# MCU.net
KiCad netlist of a schematic drawn in Altium Designer
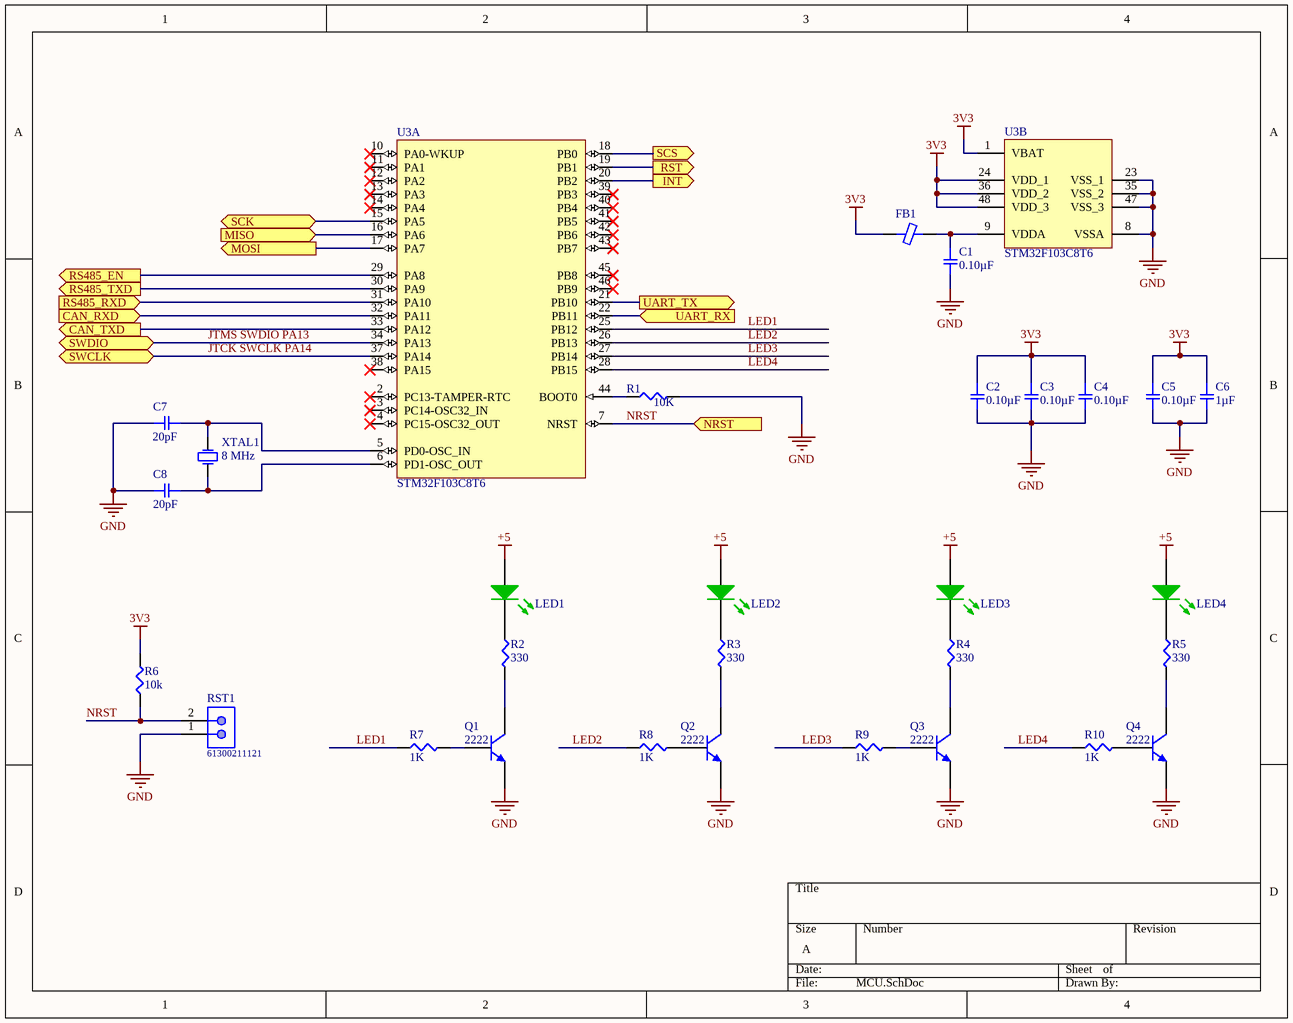
[diagram p0: MCU.SchDoc]

(export (version "E")
  (design (tool "Eeschema 10.0.6"))
  (components
    (comp (ref "C1")
      (value "0.10µF")
      (footprint "0805")
      (description "CAP CER 0.1UF 25V X7R 0805")
      (fields
        (field (name "DIGI-KEY PART NUMBER") "490-12754-1-ND")
        (field (name "PART NUMBER") "GRM219R71E104KA01D")
      )
      (libsource (lib "Cap_805") (part "GRM219R71E104KA01D"))
    )
    (comp (ref "C2")
      (value "0.10µF")
      (footprint "0805")
      (description "CAP CER 0.1UF 25V X7R 0805")
      (fields
        (field (name "DIGI-KEY PART NUMBER") "490-12754-1-ND")
        (field (name "PART NUMBER") "GRM219R71E104KA01D")
      )
      (libsource (lib "Cap_805") (part "GRM219R71E104KA01D"))
    )
    (comp (ref "C3")
      (value "0.10µF")
      (footprint "0805")
      (description "CAP CER 0.1UF 25V X7R 0805")
      (fields
        (field (name "DIGI-KEY PART NUMBER") "490-12754-1-ND")
        (field (name "PART NUMBER") "GRM219R71E104KA01D")
      )
      (libsource (lib "Cap_805") (part "GRM219R71E104KA01D"))
    )
    (comp (ref "C4")
      (value "0.10µF")
      (footprint "0805")
      (description "CAP CER 0.1UF 25V X7R 0805")
      (fields
        (field (name "DIGI-KEY PART NUMBER") "490-12754-1-ND")
        (field (name "PART NUMBER") "GRM219R71E104KA01D")
      )
      (libsource (lib "Cap_805") (part "GRM219R71E104KA01D"))
    )
    (comp (ref "C5")
      (value "0.10µF")
      (footprint "0805")
      (description "CAP CER 0.1UF 25V X7R 0805")
      (fields
        (field (name "DIGI-KEY PART NUMBER") "490-12754-1-ND")
        (field (name "PART NUMBER") "GRM219R71E104KA01D")
      )
      (libsource (lib "Cap_805") (part "GRM219R71E104KA01D"))
    )
    (comp (ref "C6")
      (value "1µF")
      (footprint "0805")
      (description "CAP CER 1.0UF 16V X7R 0805")
      (fields
        (field (name "DIGI-KEY PART NUMBER") "490-12590-1-ND")
        (field (name "PART NUMBER") "GCM219R71C105KA37J")
      )
      (libsource (lib "Cap_805") (part "GCM219R71C105KA37J"))
    )
    (comp (ref "C7")
      (value "20pF")
      (footprint "0805")
      (description "CAP CER 20PF 50V NP0 0805")
      (fields
        (field (name "DIGI-KEY PART NUMBER") "490-3607-1-ND")
        (field (name "PART NUMBER") "GQM2195C1H200JB01D")
      )
      (libsource (lib "Cap_805") (part "GQM2195C1H200JB01D"))
    )
    (comp (ref "C8")
      (value "20pF")
      (footprint "0805")
      (description "CAP CER 20PF 50V NP0 0805")
      (fields
        (field (name "DIGI-KEY PART NUMBER") "490-3607-1-ND")
        (field (name "PART NUMBER") "GQM2195C1H200JB01D")
      )
      (libsource (lib "Cap_805") (part "GQM2195C1H200JB01D"))
    )
    (comp (ref "FB1")
      (value "~")
      (footprint "0805")
      (description "FERRITE BEAD 0805 1LN")
      (fields
        (field (name "PART NUMBER") "2508053007Y3")
        (field (name "MANUFACTURER") "Fair-Rite Products Corp.")
      )
      (libsource (lib "Celestial Altium Library - altium_library") (part "Ferrite Chip"))
    )
    (comp (ref "LED1")
      (value "LED-GREEN")
      (footprint "DIOSMD1206")
      (description "General Propuse Ga/As LED")
      (libsource (lib "GeneralLibrary") (part "LED-GREEN"))
    )
    (comp (ref "LED2")
      (value "LED-GREEN")
      (footprint "DIOSMD1206")
      (description "General Propuse Ga/As LED")
      (libsource (lib "GeneralLibrary") (part "LED-GREEN"))
    )
    (comp (ref "LED3")
      (value "LED-GREEN")
      (footprint "DIOSMD1206")
      (description "General Propuse Ga/As LED")
      (libsource (lib "GeneralLibrary") (part "LED-GREEN"))
    )
    (comp (ref "LED4")
      (value "LED-GREEN")
      (footprint "DIOSMD1206")
      (description "General Propuse Ga/As LED")
      (libsource (lib "GeneralLibrary") (part "LED-GREEN"))
    )
    (comp (ref "Q1")
      (value "2222")
      (footprint "SOT23-3")
      (description "NPN General Purpose Amplifier")
      (fields (field (name "PUBLISHER") "Altium Limited"))
      (libsource (lib "GeneralLibrary") (part "BC817-25"))
    )
    (comp (ref "Q2")
      (value "2222")
      (footprint "SOT23-3")
      (description "NPN General Purpose Amplifier")
      (fields (field (name "PUBLISHER") "Altium Limited"))
      (libsource (lib "GeneralLibrary") (part "BC817-25"))
    )
    (comp (ref "Q3")
      (value "2222")
      (footprint "SOT23-3")
      (description "NPN General Purpose Amplifier")
      (fields (field (name "PUBLISHER") "Altium Limited"))
      (libsource (lib "GeneralLibrary") (part "BC817-25"))
    )
    (comp (ref "Q4")
      (value "2222")
      (footprint "SOT23-3")
      (description "NPN General Purpose Amplifier")
      (fields (field (name "PUBLISHER") "Altium Limited"))
      (libsource (lib "GeneralLibrary") (part "BC817-25"))
    )
    (comp (ref "R1")
      (value "10K")
      (footprint "0805")
      (description "RES SMD 10K OHM 5% 1/8W 0805")
      (fields (field (name "PART NUMBER") "ERJ-6GEYJ103V") (field (name "DIGI-KEY PART NUMBER") "P10KACT-ND"))
      (libsource (lib "Res_805") (part "ERJ-6GEYJ103V"))
    )
    (comp (ref "R2")
      (value "330")
      (footprint "0805")
      (description "RES SMD 330 OHM 5% 1/8W 0805")
      (fields (field (name "PART NUMBER") "ERJ-6GEYJ331V") (field (name "DIGI-KEY PART NUMBER") "P330ACT-ND"))
      (libsource (lib "Res_805") (part "ERJ-6GEYJ331V"))
    )
    (comp (ref "R3")
      (value "330")
      (footprint "0805")
      (description "RES SMD 330 OHM 5% 1/8W 0805")
      (fields (field (name "PART NUMBER") "ERJ-6GEYJ331V") (field (name "DIGI-KEY PART NUMBER") "P330ACT-ND"))
      (libsource (lib "Res_805") (part "ERJ-6GEYJ331V"))
    )
    (comp (ref "R4")
      (value "330")
      (footprint "0805")
      (description "RES SMD 330 OHM 5% 1/8W 0805")
      (fields (field (name "PART NUMBER") "ERJ-6GEYJ331V") (field (name "DIGI-KEY PART NUMBER") "P330ACT-ND"))
      (libsource (lib "Res_805") (part "ERJ-6GEYJ331V"))
    )
    (comp (ref "R5")
      (value "330")
      (footprint "0805")
      (description "RES SMD 330 OHM 5% 1/8W 0805")
      (fields (field (name "PART NUMBER") "ERJ-6GEYJ331V") (field (name "DIGI-KEY PART NUMBER") "P330ACT-ND"))
      (libsource (lib "Res_805") (part "ERJ-6GEYJ331V"))
    )
    (comp (ref "R6")
      (value "10k")
      (footprint "0805")
      (description "RES SMD 10K OHM 5% 1/8W 0805")
      (fields (field (name "PART NUMBER") "ERJ-6GEYJ103V") (field (name "DIGI-KEY PART NUMBER") "P10KACT-ND"))
      (libsource (lib "Res_805") (part "ERJ-6GEYJ103V"))
    )
    (comp (ref "R7")
      (value "1K")
      (footprint "0805")
      (description "RES SMD 330 OHM 5% 1/8W 0805")
      (fields (field (name "PART NUMBER") "ERJ-6GEYJ331V") (field (name "DIGI-KEY PART NUMBER") "P330ACT-ND"))
      (libsource (lib "Res_805") (part "ERJ-6GEYJ331V"))
    )
    (comp (ref "R8")
      (value "1K")
      (footprint "0805")
      (description "RES SMD 330 OHM 5% 1/8W 0805")
      (fields (field (name "PART NUMBER") "ERJ-6GEYJ331V") (field (name "DIGI-KEY PART NUMBER") "P330ACT-ND"))
      (libsource (lib "Res_805") (part "ERJ-6GEYJ331V"))
    )
    (comp (ref "R9")
      (value "1K")
      (footprint "0805")
      (description "RES SMD 330 OHM 5% 1/8W 0805")
      (fields (field (name "PART NUMBER") "ERJ-6GEYJ331V") (field (name "DIGI-KEY PART NUMBER") "P330ACT-ND"))
      (libsource (lib "Res_805") (part "ERJ-6GEYJ331V"))
    )
    (comp (ref "R10")
      (value "1K")
      (footprint "0805")
      (description "RES SMD 330 OHM 5% 1/8W 0805")
      (fields (field (name "PART NUMBER") "ERJ-6GEYJ331V") (field (name "DIGI-KEY PART NUMBER") "P330ACT-ND"))
      (libsource (lib "Res_805") (part "ERJ-6GEYJ331V"))
    )
    (comp (ref "RST1")
      (value "61300211121")
      (footprint "61300211121")
      (description "WR-PHD Pin Header, THT, pitch 2.54mm, Single Row, Vertical, 2pin")
      (fields (field (name "PUBLISHER") "Wurth Elektronik"))
      (libsource (lib "PinHeader") (part "61300211121"))
    )
    (comp (ref "U3")
      (value "STM32F103C8T6")
      (footprint "STM-LQFP48_N")
      (libsource (lib "STM32F1") (part "STM32F103C8T6"))
    )
    (comp (ref "XTAL1")
      (value "8 MHz")
      (footprint "CRYSTAL Small")
      (description "XTAL Crystal")
      (fields (field (name "DESIGNER") "ABBAS BASEREH"))
      (libsource (lib "Altium") (part "XTAL"))
    )
  )
  (nets
    (net (code "1") (name "+5") (class "Default")
      (node (ref "LED1") (pin "1") (pinfunction "A_1") (pintype "passive"))
      (node (ref "LED2") (pin "1") (pinfunction "A_1") (pintype "passive"))
      (node (ref "LED3") (pin "1") (pinfunction "A_1") (pintype "passive"))
      (node (ref "LED4") (pin "1") (pinfunction "A_1") (pintype "passive"))
    )
    (net (code "2") (name "/CAN_RXD") (class "Default")
      (node (ref "U3") (pin "32") (pinfunction "PA11_32") (pintype "bidirectional"))
    )
    (net (code "3") (name "/CAN_TXD") (class "Default")
      (node (ref "U3") (pin "33") (pinfunction "PA12_33") (pintype "bidirectional"))
    )
    (net (code "4") (name "/INT") (class "Default")
      (node (ref "U3") (pin "20") (pinfunction "PB2_20") (pintype "bidirectional"))
    )
    (net (code "5") (name "/JTCK SWCLK PA14") (class "Default")
      (node (ref "U3") (pin "37") (pinfunction "PA14_37") (pintype "bidirectional"))
    )
    (net (code "6") (name "/JTMS SWDIO PA13") (class "Default")
      (node (ref "U3") (pin "34") (pinfunction "PA13_34") (pintype "bidirectional"))
    )
    (net (code "7") (name "/LED1") (class "Default")
      (node (ref "R7") (pin "1") (pinfunction "1_1") (pintype "passive"))
      (node (ref "U3") (pin "25") (pinfunction "PB12_25") (pintype "bidirectional"))
    )
    (net (code "8") (name "/LED2") (class "Default")
      (node (ref "R8") (pin "1") (pinfunction "1_1") (pintype "passive"))
      (node (ref "U3") (pin "26") (pinfunction "PB13_26") (pintype "bidirectional"))
    )
    (net (code "9") (name "/LED3") (class "Default")
      (node (ref "R9") (pin "1") (pinfunction "1_1") (pintype "passive"))
      (node (ref "U3") (pin "27") (pinfunction "PB14_27") (pintype "bidirectional"))
    )
    (net (code "10") (name "/LED4") (class "Default")
      (node (ref "R10") (pin "1") (pinfunction "1_1") (pintype "passive"))
      (node (ref "U3") (pin "28") (pinfunction "PB15_28") (pintype "bidirectional"))
    )
    (net (code "11") (name "/MISO") (class "Default")
      (node (ref "U3") (pin "16") (pinfunction "PA6_16") (pintype "bidirectional"))
    )
    (net (code "12") (name "/MOSI") (class "Default")
      (node (ref "U3") (pin "17") (pinfunction "PA7_17") (pintype "bidirectional"))
    )
    (net (code "13") (name "/NRST") (class "Default")
      (node (ref "R6") (pin "1") (pinfunction "1_1") (pintype "passive"))
      (node (ref "RST1") (pin "2") (pinfunction "2_2") (pintype "passive"))
      (node (ref "U3") (pin "7") (pinfunction "NRST_7") (pintype "bidirectional"))
    )
    (net (code "14") (name "/RS485_EN") (class "Default")
      (node (ref "U3") (pin "29") (pinfunction "PA8_29") (pintype "bidirectional"))
    )
    (net (code "15") (name "/RS485_RXD") (class "Default")
      (node (ref "U3") (pin "31") (pinfunction "PA10_31") (pintype "bidirectional"))
    )
    (net (code "16") (name "/RS485_TXD") (class "Default")
      (node (ref "U3") (pin "30") (pinfunction "PA9_30") (pintype "bidirectional"))
    )
    (net (code "17") (name "/RST") (class "Default")
      (node (ref "U3") (pin "19") (pinfunction "PB1_19") (pintype "bidirectional"))
    )
    (net (code "18") (name "/SCK") (class "Default")
      (node (ref "U3") (pin "15") (pinfunction "PA5_15") (pintype "bidirectional"))
    )
    (net (code "19") (name "/SCS") (class "Default")
      (node (ref "U3") (pin "18") (pinfunction "PB0_18") (pintype "bidirectional"))
    )
    (net (code "20") (name "/UART_RX") (class "Default")
      (node (ref "U3") (pin "22") (pinfunction "PB11_22") (pintype "bidirectional"))
    )
    (net (code "21") (name "/UART_TX") (class "Default")
      (node (ref "U3") (pin "21") (pinfunction "PB10_21") (pintype "bidirectional"))
    )
    (net (code "22") (name "3V3") (class "Default")
      (node (ref "C2") (pin "1") (pinfunction "1_1") (pintype "passive"))
      (node (ref "C3") (pin "1") (pinfunction "1_1") (pintype "passive"))
      (node (ref "C4") (pin "1") (pinfunction "1_1") (pintype "passive"))
      (node (ref "C5") (pin "1") (pinfunction "1_1") (pintype "passive"))
      (node (ref "C6") (pin "1") (pinfunction "1_1") (pintype "passive"))
      (node (ref "FB1") (pin "1") (pinfunction "1_1") (pintype "passive"))
      (node (ref "R6") (pin "2") (pinfunction "2_2") (pintype "passive"))
      (node (ref "U3") (pin "1") (pinfunction "VBAT_1") (pintype "power_in"))
      (node (ref "U3") (pin "24") (pinfunction "VDD_1_24") (pintype "power_in"))
      (node (ref "U3") (pin "36") (pinfunction "VDD_2_36") (pintype "power_in"))
      (node (ref "U3") (pin "48") (pinfunction "VDD_3_48") (pintype "power_in"))
    )
    (net (code "23") (name "GND") (class "Default")
      (node (ref "C1") (pin "2") (pinfunction "2_2") (pintype "passive"))
      (node (ref "C2") (pin "2") (pinfunction "2_2") (pintype "passive"))
      (node (ref "C3") (pin "2") (pinfunction "2_2") (pintype "passive"))
      (node (ref "C4") (pin "2") (pinfunction "2_2") (pintype "passive"))
      (node (ref "C5") (pin "2") (pinfunction "2_2") (pintype "passive"))
      (node (ref "C6") (pin "2") (pinfunction "2_2") (pintype "passive"))
      (node (ref "C7") (pin "2") (pinfunction "2_2") (pintype "passive"))
      (node (ref "C8") (pin "2") (pinfunction "2_2") (pintype "passive"))
      (node (ref "Q1") (pin "2") (pinfunction "E_2") (pintype "passive"))
      (node (ref "Q2") (pin "2") (pinfunction "E_2") (pintype "passive"))
      (node (ref "Q3") (pin "2") (pinfunction "E_2") (pintype "passive"))
      (node (ref "Q4") (pin "2") (pinfunction "E_2") (pintype "passive"))
      (node (ref "R1") (pin "2") (pinfunction "2_2") (pintype "passive"))
      (node (ref "RST1") (pin "1") (pinfunction "1_1") (pintype "passive"))
      (node (ref "U3") (pin "23") (pinfunction "VSS_1_23") (pintype "power_in"))
      (node (ref "U3") (pin "35") (pinfunction "VSS_2_35") (pintype "power_in"))
      (node (ref "U3") (pin "47") (pinfunction "VSS_3_47") (pintype "power_in"))
      (node (ref "U3") (pin "8") (pinfunction "VSSA_8") (pintype "power_in"))
    )
    (net (code "24") (name "Net-(LED1-K)") (class "Default")
      (node (ref "LED1") (pin "2") (pinfunction "K_2") (pintype "passive"))
      (node (ref "R2") (pin "1") (pinfunction "1_1") (pintype "passive"))
    )
    (net (code "25") (name "Net-(LED2-K)") (class "Default")
      (node (ref "LED2") (pin "2") (pinfunction "K_2") (pintype "passive"))
      (node (ref "R3") (pin "1") (pinfunction "1_1") (pintype "passive"))
    )
    (net (code "26") (name "Net-(LED3-K)") (class "Default")
      (node (ref "LED3") (pin "2") (pinfunction "K_2") (pintype "passive"))
      (node (ref "R4") (pin "1") (pinfunction "1_1") (pintype "passive"))
    )
    (net (code "27") (name "Net-(LED4-K)") (class "Default")
      (node (ref "LED4") (pin "2") (pinfunction "K_2") (pintype "passive"))
      (node (ref "R5") (pin "1") (pinfunction "1_1") (pintype "passive"))
    )
    (net (code "28") (name "Net-(Q1-B)") (class "Default")
      (node (ref "Q1") (pin "1") (pinfunction "B_1") (pintype "passive"))
      (node (ref "R7") (pin "2") (pinfunction "2_2") (pintype "passive"))
    )
    (net (code "29") (name "Net-(Q1-C)") (class "Default")
      (node (ref "Q1") (pin "3") (pinfunction "C_3") (pintype "passive"))
      (node (ref "R2") (pin "2") (pinfunction "2_2") (pintype "passive"))
    )
    (net (code "30") (name "Net-(Q2-B)") (class "Default")
      (node (ref "Q2") (pin "1") (pinfunction "B_1") (pintype "passive"))
      (node (ref "R8") (pin "2") (pinfunction "2_2") (pintype "passive"))
    )
    (net (code "31") (name "Net-(Q2-C)") (class "Default")
      (node (ref "Q2") (pin "3") (pinfunction "C_3") (pintype "passive"))
      (node (ref "R3") (pin "2") (pinfunction "2_2") (pintype "passive"))
    )
    (net (code "32") (name "Net-(Q3-B)") (class "Default")
      (node (ref "Q3") (pin "1") (pinfunction "B_1") (pintype "passive"))
      (node (ref "R9") (pin "2") (pinfunction "2_2") (pintype "passive"))
    )
    (net (code "33") (name "Net-(Q3-C)") (class "Default")
      (node (ref "Q3") (pin "3") (pinfunction "C_3") (pintype "passive"))
      (node (ref "R4") (pin "2") (pinfunction "2_2") (pintype "passive"))
    )
    (net (code "34") (name "Net-(Q4-B)") (class "Default")
      (node (ref "Q4") (pin "1") (pinfunction "B_1") (pintype "passive"))
      (node (ref "R10") (pin "2") (pinfunction "2_2") (pintype "passive"))
    )
    (net (code "35") (name "Net-(Q4-C)") (class "Default")
      (node (ref "Q4") (pin "3") (pinfunction "C_3") (pintype "passive"))
      (node (ref "R5") (pin "2") (pinfunction "2_2") (pintype "passive"))
    )
    (net (code "36") (name "Net-(U3A-BOOT0)") (class "Default")
      (node (ref "R1") (pin "1") (pinfunction "1_1") (pintype "passive"))
      (node (ref "U3") (pin "44") (pinfunction "BOOT0_44") (pintype "input"))
    )
    (net (code "37") (name "Net-(U3A-PD0-OSC_IN)") (class "Default")
      (node (ref "C7") (pin "1") (pinfunction "1_1") (pintype "passive"))
      (node (ref "U3") (pin "5") (pinfunction "PD0-OSC_IN_5") (pintype "bidirectional"))
      (node (ref "XTAL1") (pin "2") (pinfunction "OSC2_2") (pintype "passive"))
    )
    (net (code "38") (name "Net-(U3A-PD1-OSC_OUT)") (class "Default")
      (node (ref "C8") (pin "1") (pinfunction "1_1") (pintype "passive"))
      (node (ref "U3") (pin "6") (pinfunction "PD1-OSC_OUT_6") (pintype "bidirectional"))
      (node (ref "XTAL1") (pin "1") (pinfunction "OSC1_1") (pintype "passive"))
    )
    (net (code "39") (name "Net-(U3B-VDDA)") (class "Default")
      (node (ref "C1") (pin "1") (pinfunction "1_1") (pintype "passive"))
      (node (ref "FB1") (pin "2") (pinfunction "2_2") (pintype "passive"))
      (node (ref "U3") (pin "9") (pinfunction "VDDA_9") (pintype "power_in"))
    )
    (net (code "40") (name "unconnected-(U3A-PA0-WKUP-Pad10)") (class "Default")
      (node (ref "U3") (pin "10") (pinfunction "PA0-WKUP_10") (pintype "bidirectional+no_connect"))
    )
    (net (code "41") (name "unconnected-(U3A-PA1-Pad11)") (class "Default")
      (node (ref "U3") (pin "11") (pinfunction "PA1_11") (pintype "bidirectional+no_connect"))
    )
    (net (code "42") (name "unconnected-(U3A-PA2-Pad12)") (class "Default")
      (node (ref "U3") (pin "12") (pinfunction "PA2_12") (pintype "bidirectional+no_connect"))
    )
    (net (code "43") (name "unconnected-(U3A-PA3-Pad13)") (class "Default")
      (node (ref "U3") (pin "13") (pinfunction "PA3_13") (pintype "bidirectional+no_connect"))
    )
    (net (code "44") (name "unconnected-(U3A-PA4-Pad14)") (class "Default")
      (node (ref "U3") (pin "14") (pinfunction "PA4_14") (pintype "bidirectional+no_connect"))
    )
    (net (code "45") (name "unconnected-(U3A-PA15-Pad38)") (class "Default")
      (node (ref "U3") (pin "38") (pinfunction "PA15_38") (pintype "bidirectional+no_connect"))
    )
    (net (code "46") (name "unconnected-(U3A-PB3-Pad39)") (class "Default")
      (node (ref "U3") (pin "39") (pinfunction "PB3_39") (pintype "bidirectional+no_connect"))
    )
    (net (code "47") (name "unconnected-(U3A-PB4-Pad40)") (class "Default")
      (node (ref "U3") (pin "40") (pinfunction "PB4_40") (pintype "bidirectional+no_connect"))
    )
    (net (code "48") (name "unconnected-(U3A-PB5-Pad41)") (class "Default")
      (node (ref "U3") (pin "41") (pinfunction "PB5_41") (pintype "bidirectional+no_connect"))
    )
    (net (code "49") (name "unconnected-(U3A-PB6-Pad42)") (class "Default")
      (node (ref "U3") (pin "42") (pinfunction "PB6_42") (pintype "bidirectional+no_connect"))
    )
    (net (code "50") (name "unconnected-(U3A-PB7-Pad43)") (class "Default")
      (node (ref "U3") (pin "43") (pinfunction "PB7_43") (pintype "bidirectional+no_connect"))
    )
    (net (code "51") (name "unconnected-(U3A-PB8-Pad45)") (class "Default")
      (node (ref "U3") (pin "45") (pinfunction "PB8_45") (pintype "bidirectional+no_connect"))
    )
    (net (code "52") (name "unconnected-(U3A-PB9-Pad46)") (class "Default")
      (node (ref "U3") (pin "46") (pinfunction "PB9_46") (pintype "bidirectional+no_connect"))
    )
    (net (code "53") (name "unconnected-(U3A-PC13-TAMPER-RTC-Pad2)") (class "Default")
      (node (ref "U3") (pin "2") (pinfunction "PC13-TAMPER-RTC_2") (pintype "bidirectional+no_connect"))
    )
    (net (code "54") (name "unconnected-(U3A-PC14-OSC32_IN-Pad3)") (class "Default")
      (node (ref "U3") (pin "3") (pinfunction "PC14-OSC32_IN_3") (pintype "bidirectional+no_connect"))
    )
    (net (code "55") (name "unconnected-(U3A-PC15-OSC32_OUT-Pad4)") (class "Default")
      (node (ref "U3") (pin "4") (pinfunction "PC15-OSC32_OUT_4") (pintype "bidirectional+no_connect"))
    )
  )
)
